# new_schematic.net
KiCad netlist of a schematic drawn in EAGLE
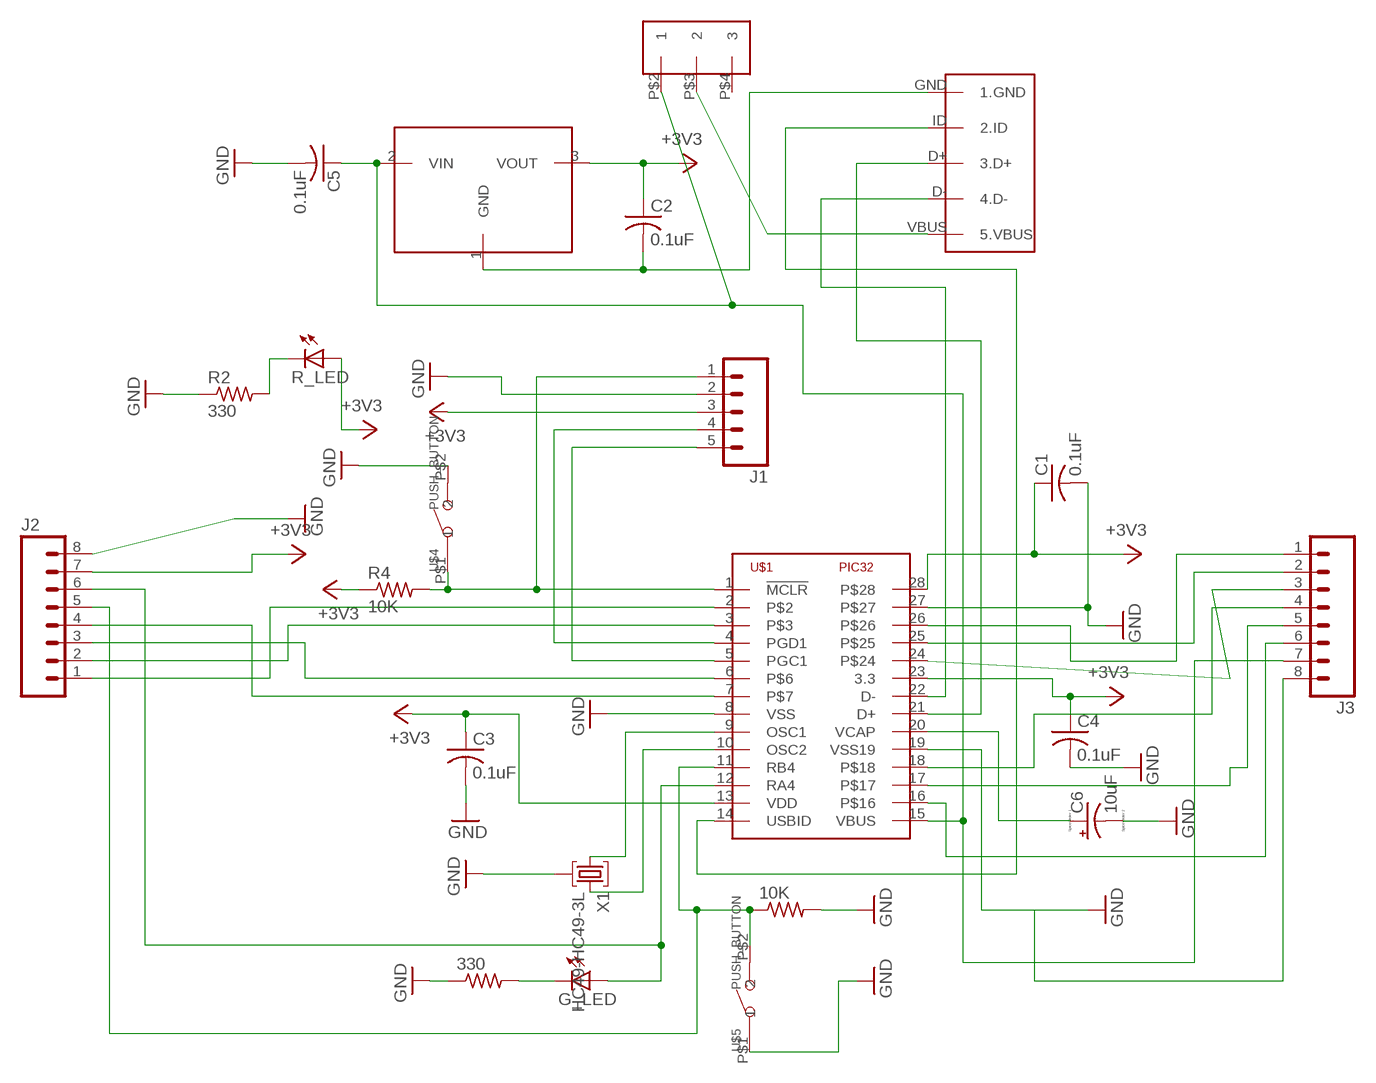
[diagram p0: schematic, sheet 1]

(export (version "E")
  (design (tool "Eeschema 10.0.6"))
  (components
    (comp (ref "10K")
      (value "R-US_0207/10")
      (footprint "eagle-import:0207_10")
      (libsource (lib "eagle-import") (part "R-US_0207/10"))
    )
    (comp (ref "330")
      (value "R-US_0207/10")
      (footprint "eagle-import:0207_10")
      (libsource (lib "eagle-import") (part "R-US_0207/10"))
    )
    (comp (ref "C1")
      (value "0.1uF")
      (footprint "eagle-import:C025-025X050")
      (libsource (lib "eagle-import") (part "C-US025-025X050"))
    )
    (comp (ref "C2")
      (value "0.1uF")
      (footprint "eagle-import:C025-025X050")
      (libsource (lib "eagle-import") (part "C-US025-025X050"))
    )
    (comp (ref "C3")
      (value "0.1uF")
      (footprint "eagle-import:C025-025X050")
      (libsource (lib "eagle-import") (part "C-US025-025X050"))
    )
    (comp (ref "C4")
      (value "0.1uF")
      (footprint "eagle-import:C025-025X050")
      (libsource (lib "eagle-import") (part "C-US025-025X050"))
    )
    (comp (ref "C5")
      (value "0.1uF")
      (footprint "eagle-import:C025-025X050")
      (libsource (lib "eagle-import") (part "C-US025-025X050"))
    )
    (comp (ref "C6")
      (value "10uF")
      (footprint "eagle-import:150CLZ-0810")
      (libsource (lib "eagle-import") (part "CPOL-US150CLZ-0810"))
    )
    (comp (ref "G_LED")
      (value "LED3MM")
      (footprint "eagle-import:LED3MM")
      (libsource (lib "eagle-import") (part "LED3MM"))
    )
    (comp (ref "J1")
      (value "M05NO_SILK")
      (footprint "eagle-import:1X05_NO_SILK")
      (libsource (lib "eagle-import") (part "M05NO_SILK"))
    )
    (comp (ref "J2")
      (value "M08")
      (footprint "eagle-import:1X08_ROUND")
      (libsource (lib "eagle-import") (part "M08"))
    )
    (comp (ref "J3")
      (value "M08")
      (footprint "eagle-import:1X08_ROUND")
      (libsource (lib "eagle-import") (part "M08"))
    )
    (comp (ref "R2")
      (value "330")
      (footprint "eagle-import:0207_10")
      (libsource (lib "eagle-import") (part "R-US_0207/10"))
    )
    (comp (ref "R4")
      (value "10K")
      (footprint "eagle-import:0207_10")
      (libsource (lib "eagle-import") (part "R-US_0207/10"))
    )
    (comp (ref "R_LED")
      (value "LED3MM")
      (footprint "eagle-import:LED3MM")
      (libsource (lib "eagle-import") (part "LED3MM"))
    )
    (comp (ref "U$1")
      (value "PIC32")
      (footprint "eagle-import:DIL28-3")
      (libsource (lib "eagle-import") (part "PIC32"))
    )
    (comp (ref "U$2")
      (value "MINI_USB")
      (footprint "eagle-import:USB-MB-H")
      (libsource (lib "eagle-import") (part "MINI_USB"))
    )
    (comp (ref "U$3")
      (value "SLIDE_SWITCH")
      (footprint "eagle-import:SLIDE_SWITCH")
      (libsource (lib "eagle-import") (part "SLIDE_SWITCH"))
    )
    (comp (ref "U$4")
      (value "PUSH_BUTTON")
      (footprint "eagle-import:PUSH_BUTTON")
      (libsource (lib "eagle-import") (part "PUSH_BUTTON"))
    )
    (comp (ref "U$5")
      (value "PUSH_BUTTON")
      (footprint "eagle-import:PUSH_BUTTON")
      (libsource (lib "eagle-import") (part "PUSH_BUTTON"))
    )
    (comp (ref "U$9")
      (value "MCP1702")
      (footprint "eagle-import:TO92")
      (libsource (lib "eagle-import") (part "MCP1702"))
    )
    (comp (ref "X1")
      (value "HC49-HC49-3L")
      (footprint "eagle-import:HC49-3L")
      (libsource (lib "eagle-import") (part "HC49-HC49-3L"))
    )
  )
  (nets
    (net (code "1") (name "+3V3") (class "Default")
      (node (ref "C1") (pin "1") (pinfunction "1_1") (pintype "passive"))
      (node (ref "C2") (pin "1") (pinfunction "1_1") (pintype "passive"))
      (node (ref "C3") (pin "1") (pinfunction "1_1") (pintype "passive"))
      (node (ref "C4") (pin "1") (pinfunction "1_1") (pintype "passive"))
      (node (ref "J1") (pin "3") (pinfunction "3_3") (pintype "passive"))
      (node (ref "J2") (pin "7") (pinfunction "7_7") (pintype "passive"))
      (node (ref "R4") (pin "1") (pinfunction "1_1") (pintype "passive"))
      (node (ref "R_LED") (pin "A") (pinfunction "A_A") (pintype "passive"))
      (node (ref "U$1") (pin "13") (pinfunction "VDD_13") (pintype "bidirectional"))
      (node (ref "U$1") (pin "23") (pinfunction "3.3_23") (pintype "bidirectional"))
      (node (ref "U$1") (pin "28") (pinfunction "P$28_28") (pintype "bidirectional"))
      (node (ref "U$9") (pin "3") (pinfunction "VOUT_3") (pintype "bidirectional"))
    )
    (net (code "2") (name "GND") (class "Default")
      (node (ref "10K") (pin "2") (pinfunction "2_2") (pintype "passive"))
      (node (ref "330") (pin "1") (pinfunction "1_1") (pintype "passive"))
      (node (ref "C1") (pin "2") (pinfunction "2_2") (pintype "passive"))
      (node (ref "C3") (pin "2") (pinfunction "2_2") (pintype "passive"))
      (node (ref "C4") (pin "2") (pinfunction "2_2") (pintype "passive"))
      (node (ref "C5") (pin "2") (pinfunction "2_2") (pintype "passive"))
      (node (ref "C6") (pin "-") (pinfunction "-_-") (pintype "passive"))
      (node (ref "J1") (pin "2") (pinfunction "2_2") (pintype "passive"))
      (node (ref "J2") (pin "8") (pinfunction "8_8") (pintype "passive"))
      (node (ref "J3") (pin "8") (pinfunction "8_8") (pintype "passive"))
      (node (ref "R2") (pin "1") (pinfunction "1_1") (pintype "passive"))
      (node (ref "U$1") (pin "19") (pinfunction "VSS19_19") (pintype "bidirectional"))
      (node (ref "U$1") (pin "27") (pinfunction "P$27_27") (pintype "bidirectional"))
      (node (ref "U$1") (pin "8") (pinfunction "VSS_8") (pintype "bidirectional"))
      (node (ref "U$4") (pin "P$2") (pinfunction "2_P$2") (pintype "bidirectional"))
      (node (ref "U$5") (pin "P$1") (pinfunction "1_P$1") (pintype "bidirectional"))
      (node (ref "X1") (pin "2") (pinfunction "2_2") (pintype "passive"))
    )
    (net (code "3") (name "Net-(G_LED-C)") (class "Default")
      (node (ref "330") (pin "2") (pinfunction "2_2") (pintype "passive"))
      (node (ref "G_LED") (pin "K") (pinfunction "C_K") (pintype "passive"))
    )
    (net (code "4") (name "Net-(R_LED-C)") (class "Default")
      (node (ref "R2") (pin "2") (pinfunction "2_2") (pintype "passive"))
      (node (ref "R_LED") (pin "K") (pinfunction "C_K") (pintype "passive"))
    )
    (net (code "5") (name "Net-(U$1-D+)") (class "Default")
      (node (ref "U$1") (pin "21") (pinfunction "D+_21") (pintype "bidirectional"))
      (node (ref "U$2") (pin "D+") (pinfunction "3.D+_D+") (pintype "bidirectional"))
    )
    (net (code "6") (name "Net-(U$1-D-)") (class "Default")
      (node (ref "U$1") (pin "22") (pinfunction "D-_22") (pintype "bidirectional"))
      (node (ref "U$2") (pin "D-") (pinfunction "4.D-_D-") (pintype "bidirectional"))
    )
    (net (code "7") (name "Net-(U$1-OSC1)") (class "Default")
      (node (ref "U$1") (pin "9") (pinfunction "OSC1_9") (pintype "bidirectional"))
      (node (ref "X1") (pin "1") (pinfunction "1_1") (pintype "passive"))
    )
    (net (code "8") (name "Net-(U$1-OSC2)") (class "Default")
      (node (ref "U$1") (pin "10") (pinfunction "OSC2_10") (pintype "bidirectional"))
      (node (ref "X1") (pin "3") (pinfunction "3_3") (pintype "passive"))
    )
    (net (code "9") (name "Net-(U$1-P$2)") (class "Default")
      (node (ref "J2") (pin "1") (pinfunction "1_1") (pintype "passive"))
      (node (ref "U$1") (pin "2") (pinfunction "P$2_2") (pintype "bidirectional"))
    )
    (net (code "10") (name "Net-(U$1-P$3)") (class "Default")
      (node (ref "J2") (pin "2") (pinfunction "2_2") (pintype "passive"))
      (node (ref "U$1") (pin "3") (pinfunction "P$3_3") (pintype "bidirectional"))
    )
    (net (code "11") (name "Net-(U$1-P$6)") (class "Default")
      (node (ref "J2") (pin "3") (pinfunction "3_3") (pintype "passive"))
      (node (ref "U$1") (pin "6") (pinfunction "P$6_6") (pintype "bidirectional"))
    )
    (net (code "12") (name "Net-(U$1-P$7)") (class "Default")
      (node (ref "J2") (pin "4") (pinfunction "4_4") (pintype "passive"))
      (node (ref "U$1") (pin "7") (pinfunction "P$7_7") (pintype "bidirectional"))
    )
    (net (code "13") (name "Net-(U$1-P$16)") (class "Default")
      (node (ref "J3") (pin "6") (pinfunction "6_6") (pintype "passive"))
      (node (ref "U$1") (pin "16") (pinfunction "P$16_16") (pintype "bidirectional"))
    )
    (net (code "14") (name "Net-(U$1-P$17)") (class "Default")
      (node (ref "J3") (pin "5") (pinfunction "5_5") (pintype "passive"))
      (node (ref "U$1") (pin "17") (pinfunction "P$17_17") (pintype "bidirectional"))
    )
    (net (code "15") (name "Net-(U$1-P$18)") (class "Default")
      (node (ref "J3") (pin "4") (pinfunction "4_4") (pintype "passive"))
      (node (ref "U$1") (pin "18") (pinfunction "P$18_18") (pintype "bidirectional"))
    )
    (net (code "16") (name "Net-(U$1-P$24)") (class "Default")
      (node (ref "J3") (pin "3") (pinfunction "3_3") (pintype "passive"))
      (node (ref "U$1") (pin "24") (pinfunction "P$24_24") (pintype "bidirectional"))
    )
    (net (code "17") (name "Net-(U$1-P$25)") (class "Default")
      (node (ref "J3") (pin "2") (pinfunction "2_2") (pintype "passive"))
      (node (ref "U$1") (pin "25") (pinfunction "P$25_25") (pintype "bidirectional"))
    )
    (net (code "18") (name "Net-(U$1-P$26)") (class "Default")
      (node (ref "J3") (pin "1") (pinfunction "1_1") (pintype "passive"))
      (node (ref "U$1") (pin "26") (pinfunction "P$26_26") (pintype "bidirectional"))
    )
    (net (code "19") (name "Net-(U$1-PGC1)") (class "Default")
      (node (ref "J1") (pin "5") (pinfunction "5_5") (pintype "passive"))
      (node (ref "U$1") (pin "5") (pinfunction "PGC1_5") (pintype "bidirectional"))
    )
    (net (code "20") (name "Net-(U$1-PGD1)") (class "Default")
      (node (ref "J1") (pin "4") (pinfunction "4_4") (pintype "passive"))
      (node (ref "U$1") (pin "4") (pinfunction "PGD1_4") (pintype "bidirectional"))
    )
    (net (code "21") (name "Net-(U$1-RA4)") (class "Default")
      (node (ref "G_LED") (pin "A") (pinfunction "A_A") (pintype "passive"))
      (node (ref "J2") (pin "6") (pinfunction "6_6") (pintype "passive"))
      (node (ref "U$1") (pin "12") (pinfunction "RA4_12") (pintype "bidirectional"))
    )
    (net (code "22") (name "Net-(U$1-RB4)") (class "Default")
      (node (ref "10K") (pin "1") (pinfunction "1_1") (pintype "passive"))
      (node (ref "J2") (pin "5") (pinfunction "5_5") (pintype "passive"))
      (node (ref "U$1") (pin "11") (pinfunction "RB4_11") (pintype "bidirectional"))
      (node (ref "U$5") (pin "P$2") (pinfunction "2_P$2") (pintype "bidirectional"))
    )
    (net (code "23") (name "Net-(U$1-USBID)") (class "Default")
      (node (ref "U$1") (pin "14") (pinfunction "USBID_14") (pintype "bidirectional"))
      (node (ref "U$2") (pin "ID") (pinfunction "2.ID_ID") (pintype "bidirectional"))
    )
    (net (code "24") (name "Net-(U$1-VBUS)") (class "Default")
      (node (ref "C5") (pin "1") (pinfunction "1_1") (pintype "passive"))
      (node (ref "J3") (pin "7") (pinfunction "7_7") (pintype "passive"))
      (node (ref "U$1") (pin "15") (pinfunction "VBUS_15") (pintype "bidirectional"))
      (node (ref "U$3") (pin "P$2") (pinfunction "1_P$2") (pintype "bidirectional"))
      (node (ref "U$9") (pin "2") (pinfunction "VIN_2") (pintype "bidirectional"))
    )
    (net (code "25") (name "Net-(U$1-VCAP)") (class "Default")
      (node (ref "C6") (pin "+") (pinfunction "+_+") (pintype "passive"))
      (node (ref "U$1") (pin "20") (pinfunction "VCAP_20") (pintype "bidirectional"))
    )
    (net (code "26") (name "Net-(U$1-~{MCLR})") (class "Default")
      (node (ref "J1") (pin "1") (pinfunction "1_1") (pintype "passive"))
      (node (ref "R4") (pin "2") (pinfunction "2_2") (pintype "passive"))
      (node (ref "U$1") (pin "1") (pinfunction "~{MCLR}_1") (pintype "bidirectional"))
      (node (ref "U$4") (pin "P$1") (pinfunction "1_P$1") (pintype "bidirectional"))
    )
    (net (code "27") (name "Net-(U$2-1.GND)") (class "Default")
      (node (ref "C2") (pin "2") (pinfunction "2_2") (pintype "passive"))
      (node (ref "U$2") (pin "GND") (pinfunction "1.GND_GND") (pintype "bidirectional"))
      (node (ref "U$9") (pin "1") (pinfunction "GND_1") (pintype "bidirectional"))
    )
    (net (code "28") (name "Net-(U$2-5.VBUS)") (class "Default")
      (node (ref "U$2") (pin "VBUS") (pinfunction "5.VBUS_VBUS") (pintype "bidirectional"))
      (node (ref "U$3") (pin "P$3") (pinfunction "2_P$3") (pintype "bidirectional"))
    )
    (net (code "29") (name "unconnected-(U$3-3-PadP$4)") (class "Default")
      (node (ref "U$3") (pin "P$4") (pinfunction "3_P$4") (pintype "bidirectional"))
    )
  )
)
